# design-1v3.net
KiCad netlist of a schematic drawn in EAGLE
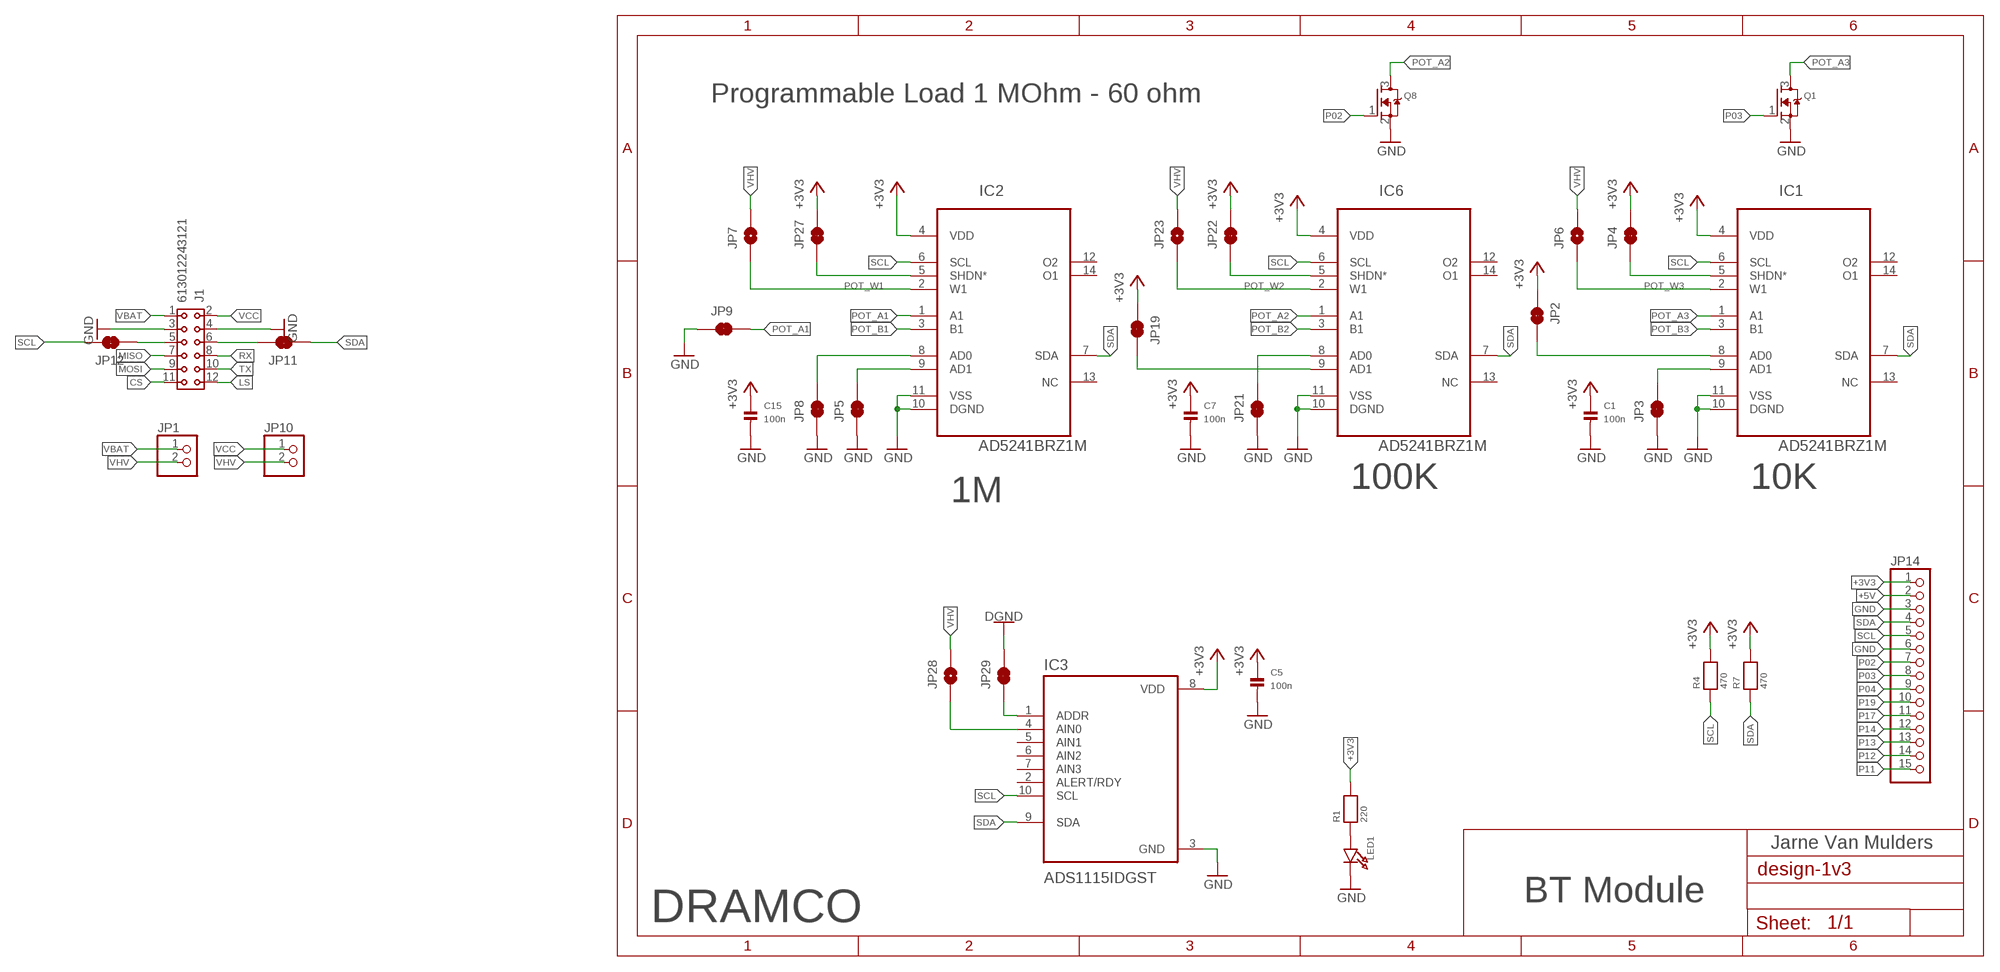
[diagram p0: schematic, sheet 1]

(export (version "E")
  (design (tool "Eeschema 10.0.6"))
  (components
    (comp (ref "C1")
      (value "100n")
      (footprint "eagle-import:0603")
      (libsource (lib "eagle-import") (part "CAP_CERAMIC0603"))
    )
    (comp (ref "C5")
      (value "100n")
      (footprint "eagle-import:0603")
      (libsource (lib "eagle-import") (part "CAP_CERAMIC0603"))
    )
    (comp (ref "C7")
      (value "100n")
      (footprint "eagle-import:0603")
      (libsource (lib "eagle-import") (part "CAP_CERAMIC0603"))
    )
    (comp (ref "C15")
      (value "100n")
      (footprint "eagle-import:0603")
      (libsource (lib "eagle-import") (part "CAP_CERAMIC0603"))
    )
    (comp (ref "IC1")
      (value "AD5241BRZ1M")
      (footprint "eagle-import:SOIC127P600X175-14N")
      (fields (field (name "MF") "Analog Devices"))
      (libsource (lib "eagle-import") (part "AD5241BRZ1M"))
    )
    (comp (ref "IC2")
      (value "AD5241BRZ1M")
      (footprint "eagle-import:SOIC127P600X175-14N")
      (fields (field (name "MF") "Analog Devices"))
      (libsource (lib "eagle-import") (part "AD5241BRZ1M"))
    )
    (comp (ref "IC3")
      (value "ADS1115IDGST")
      (footprint "eagle-import:SOP50P490X110-10N")
      (fields (field (name "MF") "Texas Instruments"))
      (libsource (lib "eagle-import") (part "ADS1115IDGST"))
    )
    (comp (ref "IC6")
      (value "AD5241BRZ1M")
      (footprint "eagle-import:SOIC127P600X175-14N")
      (fields (field (name "MF") "Analog Devices"))
      (libsource (lib "eagle-import") (part "AD5241BRZ1M"))
    )
    (comp (ref "J1")
      (value "613012243121")
      (footprint "eagle-import:613012243121")
      (libsource (lib "eagle-import") (part "6130XX243121_613012243121"))
    )
    (comp (ref "JP1")
      (value "HEADER-1X2ROUND")
      (footprint "eagle-import:1X02_ROUND")
      (libsource (lib "eagle-import") (part "HEADER-1X2ROUND"))
    )
    (comp (ref "JP2")
      (value "JUMPER-SMT_2_NC_TRACE_NO-SILK")
      (footprint "eagle-import:SMT-JUMPER_2_NC_TRACE_NO-SILK")
      (libsource (lib "eagle-import") (part "JUMPER-SMT_2_NC_TRACE_NO-SILK"))
    )
    (comp (ref "JP3")
      (value "JUMPER-SMT_2_NC_TRACE_NO-SILK")
      (footprint "eagle-import:SMT-JUMPER_2_NC_TRACE_NO-SILK")
      (libsource (lib "eagle-import") (part "JUMPER-SMT_2_NC_TRACE_NO-SILK"))
    )
    (comp (ref "JP4")
      (value "JUMPER-SMT_2_NC_TRACE_NO-SILK")
      (footprint "eagle-import:SMT-JUMPER_2_NC_TRACE_NO-SILK")
      (libsource (lib "eagle-import") (part "JUMPER-SMT_2_NC_TRACE_NO-SILK"))
    )
    (comp (ref "JP5")
      (value "JUMPER-SMT_2_NC_TRACE_NO-SILK")
      (footprint "eagle-import:SMT-JUMPER_2_NC_TRACE_NO-SILK")
      (libsource (lib "eagle-import") (part "JUMPER-SMT_2_NC_TRACE_NO-SILK"))
    )
    (comp (ref "JP6")
      (value "JUMPER-SMT_2_NO_NO-SILK")
      (footprint "eagle-import:SMT-JUMPER_2_NO_NO-SILK")
      (libsource (lib "eagle-import") (part "JUMPER-SMT_2_NO_NO-SILK"))
    )
    (comp (ref "JP7")
      (value "JUMPER-SMT_2_NO_NO-SILK")
      (footprint "eagle-import:SMT-JUMPER_2_NO_NO-SILK")
      (libsource (lib "eagle-import") (part "JUMPER-SMT_2_NO_NO-SILK"))
    )
    (comp (ref "JP8")
      (value "JUMPER-SMT_2_NC_TRACE_NO-SILK")
      (footprint "eagle-import:SMT-JUMPER_2_NC_TRACE_NO-SILK")
      (libsource (lib "eagle-import") (part "JUMPER-SMT_2_NC_TRACE_NO-SILK"))
    )
    (comp (ref "JP9")
      (value "JUMPER-SMT_2_NC_TRACE_NO-SILK")
      (footprint "eagle-import:SMT-JUMPER_2_NC_TRACE_NO-SILK")
      (libsource (lib "eagle-import") (part "JUMPER-SMT_2_NC_TRACE_NO-SILK"))
    )
    (comp (ref "JP10")
      (value "HEADER-1X2ROUND")
      (footprint "eagle-import:1X02_ROUND")
      (libsource (lib "eagle-import") (part "HEADER-1X2ROUND"))
    )
    (comp (ref "JP11")
      (value "JUMPER-SMT_2_NC_TRACE_NO-SILK")
      (footprint "eagle-import:SMT-JUMPER_2_NC_TRACE_NO-SILK")
      (libsource (lib "eagle-import") (part "JUMPER-SMT_2_NC_TRACE_NO-SILK"))
    )
    (comp (ref "JP12")
      (value "JUMPER-SMT_2_NC_TRACE_NO-SILK")
      (footprint "eagle-import:SMT-JUMPER_2_NC_TRACE_NO-SILK")
      (libsource (lib "eagle-import") (part "JUMPER-SMT_2_NC_TRACE_NO-SILK"))
    )
    (comp (ref "JP14")
      (value "HEADER-1X15")
      (footprint "eagle-import:1X15_ROUND_70")
      (libsource (lib "eagle-import") (part "HEADER-1X15"))
    )
    (comp (ref "JP19")
      (value "JUMPER-SMT_2_NC_TRACE_NO-SILK")
      (footprint "eagle-import:SMT-JUMPER_2_NC_TRACE_NO-SILK")
      (libsource (lib "eagle-import") (part "JUMPER-SMT_2_NC_TRACE_NO-SILK"))
    )
    (comp (ref "JP21")
      (value "JUMPER-SMT_2_NC_TRACE_NO-SILK")
      (footprint "eagle-import:SMT-JUMPER_2_NC_TRACE_NO-SILK")
      (libsource (lib "eagle-import") (part "JUMPER-SMT_2_NC_TRACE_NO-SILK"))
    )
    (comp (ref "JP22")
      (value "JUMPER-SMT_2_NC_TRACE_NO-SILK")
      (footprint "eagle-import:SMT-JUMPER_2_NC_TRACE_NO-SILK")
      (libsource (lib "eagle-import") (part "JUMPER-SMT_2_NC_TRACE_NO-SILK"))
    )
    (comp (ref "JP23")
      (value "JUMPER-SMT_2_NO_NO-SILK")
      (footprint "eagle-import:SMT-JUMPER_2_NO_NO-SILK")
      (libsource (lib "eagle-import") (part "JUMPER-SMT_2_NO_NO-SILK"))
    )
    (comp (ref "JP27")
      (value "JUMPER-SMT_2_NC_TRACE_NO-SILK")
      (footprint "eagle-import:SMT-JUMPER_2_NC_TRACE_NO-SILK")
      (libsource (lib "eagle-import") (part "JUMPER-SMT_2_NC_TRACE_NO-SILK"))
    )
    (comp (ref "JP28")
      (value "JUMPER-SMT_2_NO_NO-SILK")
      (footprint "eagle-import:SMT-JUMPER_2_NO_NO-SILK")
      (libsource (lib "eagle-import") (part "JUMPER-SMT_2_NO_NO-SILK"))
    )
    (comp (ref "JP29")
      (value "JUMPER-SMT_2_NC_TRACE_NO-SILK")
      (footprint "eagle-import:SMT-JUMPER_2_NC_TRACE_NO-SILK")
      (libsource (lib "eagle-import") (part "JUMPER-SMT_2_NC_TRACE_NO-SILK"))
    )
    (comp (ref "LED1")
      (value "LED0805")
      (footprint "eagle-import:CHIPLED_0805")
      (libsource (lib "eagle-import") (part "LED0805"))
    )
    (comp (ref "Q1")
      (value "MOSFET-NREFLOW")
      (footprint "eagle-import:SOT23-R")
      (libsource (lib "eagle-import") (part "MOSFET-NREFLOW"))
    )
    (comp (ref "Q8")
      (value "MOSFET-NREFLOW")
      (footprint "eagle-import:SOT23-R")
      (libsource (lib "eagle-import") (part "MOSFET-NREFLOW"))
    )
    (comp (ref "R1")
      (value "220")
      (footprint "eagle-import:0603")
      (libsource (lib "eagle-import") (part "RESISTOR0603"))
    )
    (comp (ref "R4")
      (value "470")
      (footprint "eagle-import:0603")
      (libsource (lib "eagle-import") (part "RESISTOR0603"))
    )
    (comp (ref "R7")
      (value "470")
      (footprint "eagle-import:0603")
      (libsource (lib "eagle-import") (part "RESISTOR0603"))
    )
  )
  (nets
    (net (code "1") (name "+3V3") (class "Default")
      (node (ref "C1") (pin "1") (pinfunction "P$1_1") (pintype "passive"))
      (node (ref "C15") (pin "1") (pinfunction "P$1_1") (pintype "passive"))
      (node (ref "C5") (pin "1") (pinfunction "P$1_1") (pintype "passive"))
      (node (ref "C7") (pin "1") (pinfunction "P$1_1") (pintype "passive"))
      (node (ref "IC1") (pin "4") (pinfunction "VDD_4") (pintype "power_in"))
      (node (ref "IC2") (pin "4") (pinfunction "VDD_4") (pintype "power_in"))
      (node (ref "IC3") (pin "8") (pinfunction "VDD_8") (pintype "power_in"))
      (node (ref "IC6") (pin "4") (pinfunction "VDD_4") (pintype "power_in"))
      (node (ref "JP14") (pin "1") (pinfunction "1_1") (pintype "passive"))
      (node (ref "JP19") (pin "1") (pinfunction "1_1") (pintype "passive"))
      (node (ref "JP2") (pin "1") (pinfunction "1_1") (pintype "passive"))
      (node (ref "JP22") (pin "2") (pinfunction "2_2") (pintype "passive"))
      (node (ref "JP27") (pin "2") (pinfunction "2_2") (pintype "passive"))
      (node (ref "JP4") (pin "2") (pinfunction "2_2") (pintype "passive"))
      (node (ref "R1") (pin "2") (pinfunction "2_2") (pintype "passive"))
      (node (ref "R4") (pin "2") (pinfunction "2_2") (pintype "passive"))
      (node (ref "R7") (pin "2") (pinfunction "2_2") (pintype "passive"))
    )
    (net (code "2") (name "+5V") (class "Default")
      (node (ref "JP14") (pin "2") (pinfunction "2_2") (pintype "passive"))
    )
    (net (code "3") (name "/POT_W1") (class "Default")
      (node (ref "IC2") (pin "2") (pinfunction "W1_2") (pintype "passive"))
      (node (ref "JP7") (pin "1") (pinfunction "1_1") (pintype "passive"))
    )
    (net (code "4") (name "/POT_W2") (class "Default")
      (node (ref "IC6") (pin "2") (pinfunction "W1_2") (pintype "passive"))
      (node (ref "JP23") (pin "1") (pinfunction "1_1") (pintype "passive"))
    )
    (net (code "5") (name "/POT_W3") (class "Default")
      (node (ref "IC1") (pin "2") (pinfunction "W1_2") (pintype "passive"))
      (node (ref "JP6") (pin "1") (pinfunction "1_1") (pintype "passive"))
    )
    (net (code "6") (name "CS") (class "Default")
      (node (ref "J1") (pin "11") (pinfunction "11_11") (pintype "passive"))
    )
    (net (code "7") (name "GND") (class "Default")
      (node (ref "C1") (pin "2") (pinfunction "P$2_2") (pintype "passive"))
      (node (ref "C15") (pin "2") (pinfunction "P$2_2") (pintype "passive"))
      (node (ref "C5") (pin "2") (pinfunction "P$2_2") (pintype "passive"))
      (node (ref "C7") (pin "2") (pinfunction "P$2_2") (pintype "passive"))
      (node (ref "IC1") (pin "10") (pinfunction "DGND_10") (pintype "passive"))
      (node (ref "IC1") (pin "11") (pinfunction "VSS_11") (pintype "power_in"))
      (node (ref "IC2") (pin "10") (pinfunction "DGND_10") (pintype "passive"))
      (node (ref "IC2") (pin "11") (pinfunction "VSS_11") (pintype "power_in"))
      (node (ref "IC3") (pin "3") (pinfunction "GND_3") (pintype "power_in"))
      (node (ref "IC6") (pin "10") (pinfunction "DGND_10") (pintype "passive"))
      (node (ref "IC6") (pin "11") (pinfunction "VSS_11") (pintype "power_in"))
      (node (ref "J1") (pin "3") (pinfunction "3_3") (pintype "passive"))
      (node (ref "J1") (pin "4") (pinfunction "4_4") (pintype "passive"))
      (node (ref "JP14") (pin "3") (pinfunction "3_3") (pintype "passive"))
      (node (ref "JP14") (pin "6") (pinfunction "6_6") (pintype "passive"))
      (node (ref "JP21") (pin "1") (pinfunction "1_1") (pintype "passive"))
      (node (ref "JP29") (pin "2") (pinfunction "2_2") (pintype "passive"))
      (node (ref "JP3") (pin "1") (pinfunction "1_1") (pintype "passive"))
      (node (ref "JP5") (pin "1") (pinfunction "1_1") (pintype "passive"))
      (node (ref "JP8") (pin "1") (pinfunction "1_1") (pintype "passive"))
      (node (ref "JP9") (pin "1") (pinfunction "1_1") (pintype "passive"))
      (node (ref "LED1") (pin "C") (pinfunction "C_C") (pintype "passive"))
      (node (ref "Q1") (pin "2") (pinfunction "S_2") (pintype "bidirectional"))
      (node (ref "Q8") (pin "2") (pinfunction "S_2") (pintype "bidirectional"))
    )
    (net (code "8") (name "LS") (class "Default")
      (node (ref "J1") (pin "12") (pinfunction "12_12") (pintype "passive"))
    )
    (net (code "9") (name "MISO") (class "Default")
      (node (ref "J1") (pin "7") (pinfunction "7_7") (pintype "passive"))
    )
    (net (code "10") (name "MOSI") (class "Default")
      (node (ref "J1") (pin "9") (pinfunction "9_9") (pintype "passive"))
    )
    (net (code "11") (name "Net-(IC1-AD0)") (class "Default")
      (node (ref "IC1") (pin "8") (pinfunction "AD0_8") (pintype "passive"))
      (node (ref "JP2") (pin "2") (pinfunction "2_2") (pintype "passive"))
    )
    (net (code "12") (name "Net-(IC1-AD1)") (class "Default")
      (node (ref "IC1") (pin "9") (pinfunction "AD1_9") (pintype "passive"))
      (node (ref "JP3") (pin "2") (pinfunction "2_2") (pintype "passive"))
    )
    (net (code "13") (name "Net-(IC1-SHDN*)") (class "Default")
      (node (ref "IC1") (pin "5") (pinfunction "SHDN*_5") (pintype "passive"))
      (node (ref "JP4") (pin "1") (pinfunction "1_1") (pintype "passive"))
    )
    (net (code "14") (name "Net-(IC2-AD0)") (class "Default")
      (node (ref "IC2") (pin "8") (pinfunction "AD0_8") (pintype "passive"))
      (node (ref "JP8") (pin "2") (pinfunction "2_2") (pintype "passive"))
    )
    (net (code "15") (name "Net-(IC2-AD1)") (class "Default")
      (node (ref "IC2") (pin "9") (pinfunction "AD1_9") (pintype "passive"))
      (node (ref "JP5") (pin "2") (pinfunction "2_2") (pintype "passive"))
    )
    (net (code "16") (name "Net-(IC2-SHDN*)") (class "Default")
      (node (ref "IC2") (pin "5") (pinfunction "SHDN*_5") (pintype "passive"))
      (node (ref "JP27") (pin "1") (pinfunction "1_1") (pintype "passive"))
    )
    (net (code "17") (name "Net-(IC3-ADDR)") (class "Default")
      (node (ref "IC3") (pin "1") (pinfunction "ADDR_1") (pintype "input"))
      (node (ref "JP29") (pin "1") (pinfunction "1_1") (pintype "passive"))
    )
    (net (code "18") (name "Net-(IC3-AIN0)") (class "Default")
      (node (ref "IC3") (pin "4") (pinfunction "AIN0_4") (pintype "input"))
      (node (ref "JP28") (pin "1") (pinfunction "1_1") (pintype "passive"))
    )
    (net (code "19") (name "Net-(IC6-AD0)") (class "Default")
      (node (ref "IC6") (pin "8") (pinfunction "AD0_8") (pintype "passive"))
      (node (ref "JP21") (pin "2") (pinfunction "2_2") (pintype "passive"))
    )
    (net (code "20") (name "Net-(IC6-AD1)") (class "Default")
      (node (ref "IC6") (pin "9") (pinfunction "AD1_9") (pintype "passive"))
      (node (ref "JP19") (pin "2") (pinfunction "2_2") (pintype "passive"))
    )
    (net (code "21") (name "Net-(IC6-SHDN*)") (class "Default")
      (node (ref "IC6") (pin "5") (pinfunction "SHDN*_5") (pintype "passive"))
      (node (ref "JP22") (pin "1") (pinfunction "1_1") (pintype "passive"))
    )
    (net (code "22") (name "Net-(J1-Pad5)") (class "Default")
      (node (ref "J1") (pin "5") (pinfunction "5_5") (pintype "passive"))
      (node (ref "JP12") (pin "1") (pinfunction "1_1") (pintype "passive"))
    )
    (net (code "23") (name "Net-(J1-Pad6)") (class "Default")
      (node (ref "J1") (pin "6") (pinfunction "6_6") (pintype "passive"))
      (node (ref "JP11") (pin "2") (pinfunction "2_2") (pintype "passive"))
    )
    (net (code "24") (name "Net-(LED1-PadA)") (class "Default")
      (node (ref "LED1") (pin "A") (pinfunction "A_A") (pintype "passive"))
      (node (ref "R1") (pin "1") (pinfunction "1_1") (pintype "passive"))
    )
    (net (code "25") (name "P02") (class "Default")
      (node (ref "JP14") (pin "7") (pinfunction "7_7") (pintype "passive"))
      (node (ref "Q8") (pin "1") (pinfunction "G_1") (pintype "bidirectional"))
    )
    (net (code "26") (name "P03") (class "Default")
      (node (ref "JP14") (pin "8") (pinfunction "8_8") (pintype "passive"))
      (node (ref "Q1") (pin "1") (pinfunction "G_1") (pintype "bidirectional"))
    )
    (net (code "27") (name "P04") (class "Default")
      (node (ref "JP14") (pin "9") (pinfunction "9_9") (pintype "passive"))
    )
    (net (code "28") (name "P11") (class "Default")
      (node (ref "JP14") (pin "15") (pinfunction "15_15") (pintype "passive"))
    )
    (net (code "29") (name "P12") (class "Default")
      (node (ref "JP14") (pin "14") (pinfunction "14_14") (pintype "passive"))
    )
    (net (code "30") (name "P13") (class "Default")
      (node (ref "JP14") (pin "13") (pinfunction "13_13") (pintype "passive"))
    )
    (net (code "31") (name "P14") (class "Default")
      (node (ref "JP14") (pin "12") (pinfunction "12_12") (pintype "passive"))
    )
    (net (code "32") (name "P17") (class "Default")
      (node (ref "JP14") (pin "11") (pinfunction "11_11") (pintype "passive"))
    )
    (net (code "33") (name "P19") (class "Default")
      (node (ref "JP14") (pin "10") (pinfunction "10_10") (pintype "passive"))
    )
    (net (code "34") (name "POT_A1") (class "Default")
      (node (ref "IC2") (pin "1") (pinfunction "A1_1") (pintype "passive"))
      (node (ref "JP9") (pin "2") (pinfunction "2_2") (pintype "passive"))
    )
    (net (code "35") (name "POT_A2") (class "Default")
      (node (ref "IC6") (pin "1") (pinfunction "A1_1") (pintype "passive"))
      (node (ref "Q8") (pin "3") (pinfunction "D_3") (pintype "bidirectional"))
    )
    (net (code "36") (name "POT_A3") (class "Default")
      (node (ref "IC1") (pin "1") (pinfunction "A1_1") (pintype "passive"))
      (node (ref "Q1") (pin "3") (pinfunction "D_3") (pintype "bidirectional"))
    )
    (net (code "37") (name "POT_B1") (class "Default")
      (node (ref "IC2") (pin "3") (pinfunction "B1_3") (pintype "passive"))
    )
    (net (code "38") (name "POT_B2") (class "Default")
      (node (ref "IC6") (pin "3") (pinfunction "B1_3") (pintype "passive"))
    )
    (net (code "39") (name "POT_B3") (class "Default")
      (node (ref "IC1") (pin "3") (pinfunction "B1_3") (pintype "passive"))
    )
    (net (code "40") (name "RX") (class "Default")
      (node (ref "J1") (pin "8") (pinfunction "8_8") (pintype "passive"))
    )
    (net (code "41") (name "SCL") (class "Default")
      (node (ref "IC1") (pin "6") (pinfunction "SCL_6") (pintype "passive"))
      (node (ref "IC2") (pin "6") (pinfunction "SCL_6") (pintype "passive"))
      (node (ref "IC3") (pin "10") (pinfunction "SCL_10") (pintype "input"))
      (node (ref "IC6") (pin "6") (pinfunction "SCL_6") (pintype "passive"))
      (node (ref "JP12") (pin "2") (pinfunction "2_2") (pintype "passive"))
      (node (ref "JP14") (pin "5") (pinfunction "5_5") (pintype "passive"))
      (node (ref "R4") (pin "1") (pinfunction "1_1") (pintype "passive"))
    )
    (net (code "42") (name "SDA") (class "Default")
      (node (ref "IC1") (pin "7") (pinfunction "SDA_7") (pintype "passive"))
      (node (ref "IC2") (pin "7") (pinfunction "SDA_7") (pintype "passive"))
      (node (ref "IC3") (pin "9") (pinfunction "SDA_9") (pintype "bidirectional"))
      (node (ref "IC6") (pin "7") (pinfunction "SDA_7") (pintype "passive"))
      (node (ref "JP11") (pin "1") (pinfunction "1_1") (pintype "passive"))
      (node (ref "JP14") (pin "4") (pinfunction "4_4") (pintype "passive"))
      (node (ref "R7") (pin "1") (pinfunction "1_1") (pintype "passive"))
    )
    (net (code "43") (name "TX") (class "Default")
      (node (ref "J1") (pin "10") (pinfunction "10_10") (pintype "passive"))
    )
    (net (code "44") (name "VBAT") (class "Default")
      (node (ref "J1") (pin "1") (pinfunction "1_1") (pintype "passive"))
      (node (ref "JP1") (pin "1") (pinfunction "1_1") (pintype "passive"))
    )
    (net (code "45") (name "VCC") (class "Default")
      (node (ref "J1") (pin "2") (pinfunction "2_2") (pintype "passive"))
      (node (ref "JP10") (pin "1") (pinfunction "1_1") (pintype "passive"))
    )
    (net (code "46") (name "VHV") (class "Default")
      (node (ref "JP1") (pin "2") (pinfunction "2_2") (pintype "passive"))
      (node (ref "JP10") (pin "2") (pinfunction "2_2") (pintype "passive"))
      (node (ref "JP23") (pin "2") (pinfunction "2_2") (pintype "passive"))
      (node (ref "JP28") (pin "2") (pinfunction "2_2") (pintype "passive"))
      (node (ref "JP6") (pin "2") (pinfunction "2_2") (pintype "passive"))
      (node (ref "JP7") (pin "2") (pinfunction "2_2") (pintype "passive"))
    )
    (net (code "47") (name "unconnected-(IC1-NC-Pad13)") (class "Default")
      (node (ref "IC1") (pin "13") (pinfunction "NC_13") (pintype "passive"))
    )
    (net (code "48") (name "unconnected-(IC1-O1-Pad14)") (class "Default")
      (node (ref "IC1") (pin "14") (pinfunction "O1_14") (pintype "passive"))
    )
    (net (code "49") (name "unconnected-(IC1-O2-Pad12)") (class "Default")
      (node (ref "IC1") (pin "12") (pinfunction "O2_12") (pintype "passive"))
    )
    (net (code "50") (name "unconnected-(IC2-NC-Pad13)") (class "Default")
      (node (ref "IC2") (pin "13") (pinfunction "NC_13") (pintype "passive"))
    )
    (net (code "51") (name "unconnected-(IC2-O1-Pad14)") (class "Default")
      (node (ref "IC2") (pin "14") (pinfunction "O1_14") (pintype "passive"))
    )
    (net (code "52") (name "unconnected-(IC2-O2-Pad12)") (class "Default")
      (node (ref "IC2") (pin "12") (pinfunction "O2_12") (pintype "passive"))
    )
    (net (code "53") (name "unconnected-(IC3-AIN1-Pad5)") (class "Default")
      (node (ref "IC3") (pin "5") (pinfunction "AIN1_5") (pintype "input"))
    )
    (net (code "54") (name "unconnected-(IC3-AIN2-Pad6)") (class "Default")
      (node (ref "IC3") (pin "6") (pinfunction "AIN2_6") (pintype "input"))
    )
    (net (code "55") (name "unconnected-(IC3-AIN3-Pad7)") (class "Default")
      (node (ref "IC3") (pin "7") (pinfunction "AIN3_7") (pintype "input"))
    )
    (net (code "56") (name "unconnected-(IC3-ALERT{slash}RDY-Pad2)") (class "Default")
      (node (ref "IC3") (pin "2") (pinfunction "ALERT/RDY_2") (pintype "input"))
    )
    (net (code "57") (name "unconnected-(IC6-NC-Pad13)") (class "Default")
      (node (ref "IC6") (pin "13") (pinfunction "NC_13") (pintype "passive"))
    )
    (net (code "58") (name "unconnected-(IC6-O1-Pad14)") (class "Default")
      (node (ref "IC6") (pin "14") (pinfunction "O1_14") (pintype "passive"))
    )
    (net (code "59") (name "unconnected-(IC6-O2-Pad12)") (class "Default")
      (node (ref "IC6") (pin "12") (pinfunction "O2_12") (pintype "passive"))
    )
  )
)
